# Control_Schem.net
KiCad netlist of a schematic drawn in Altium Designer
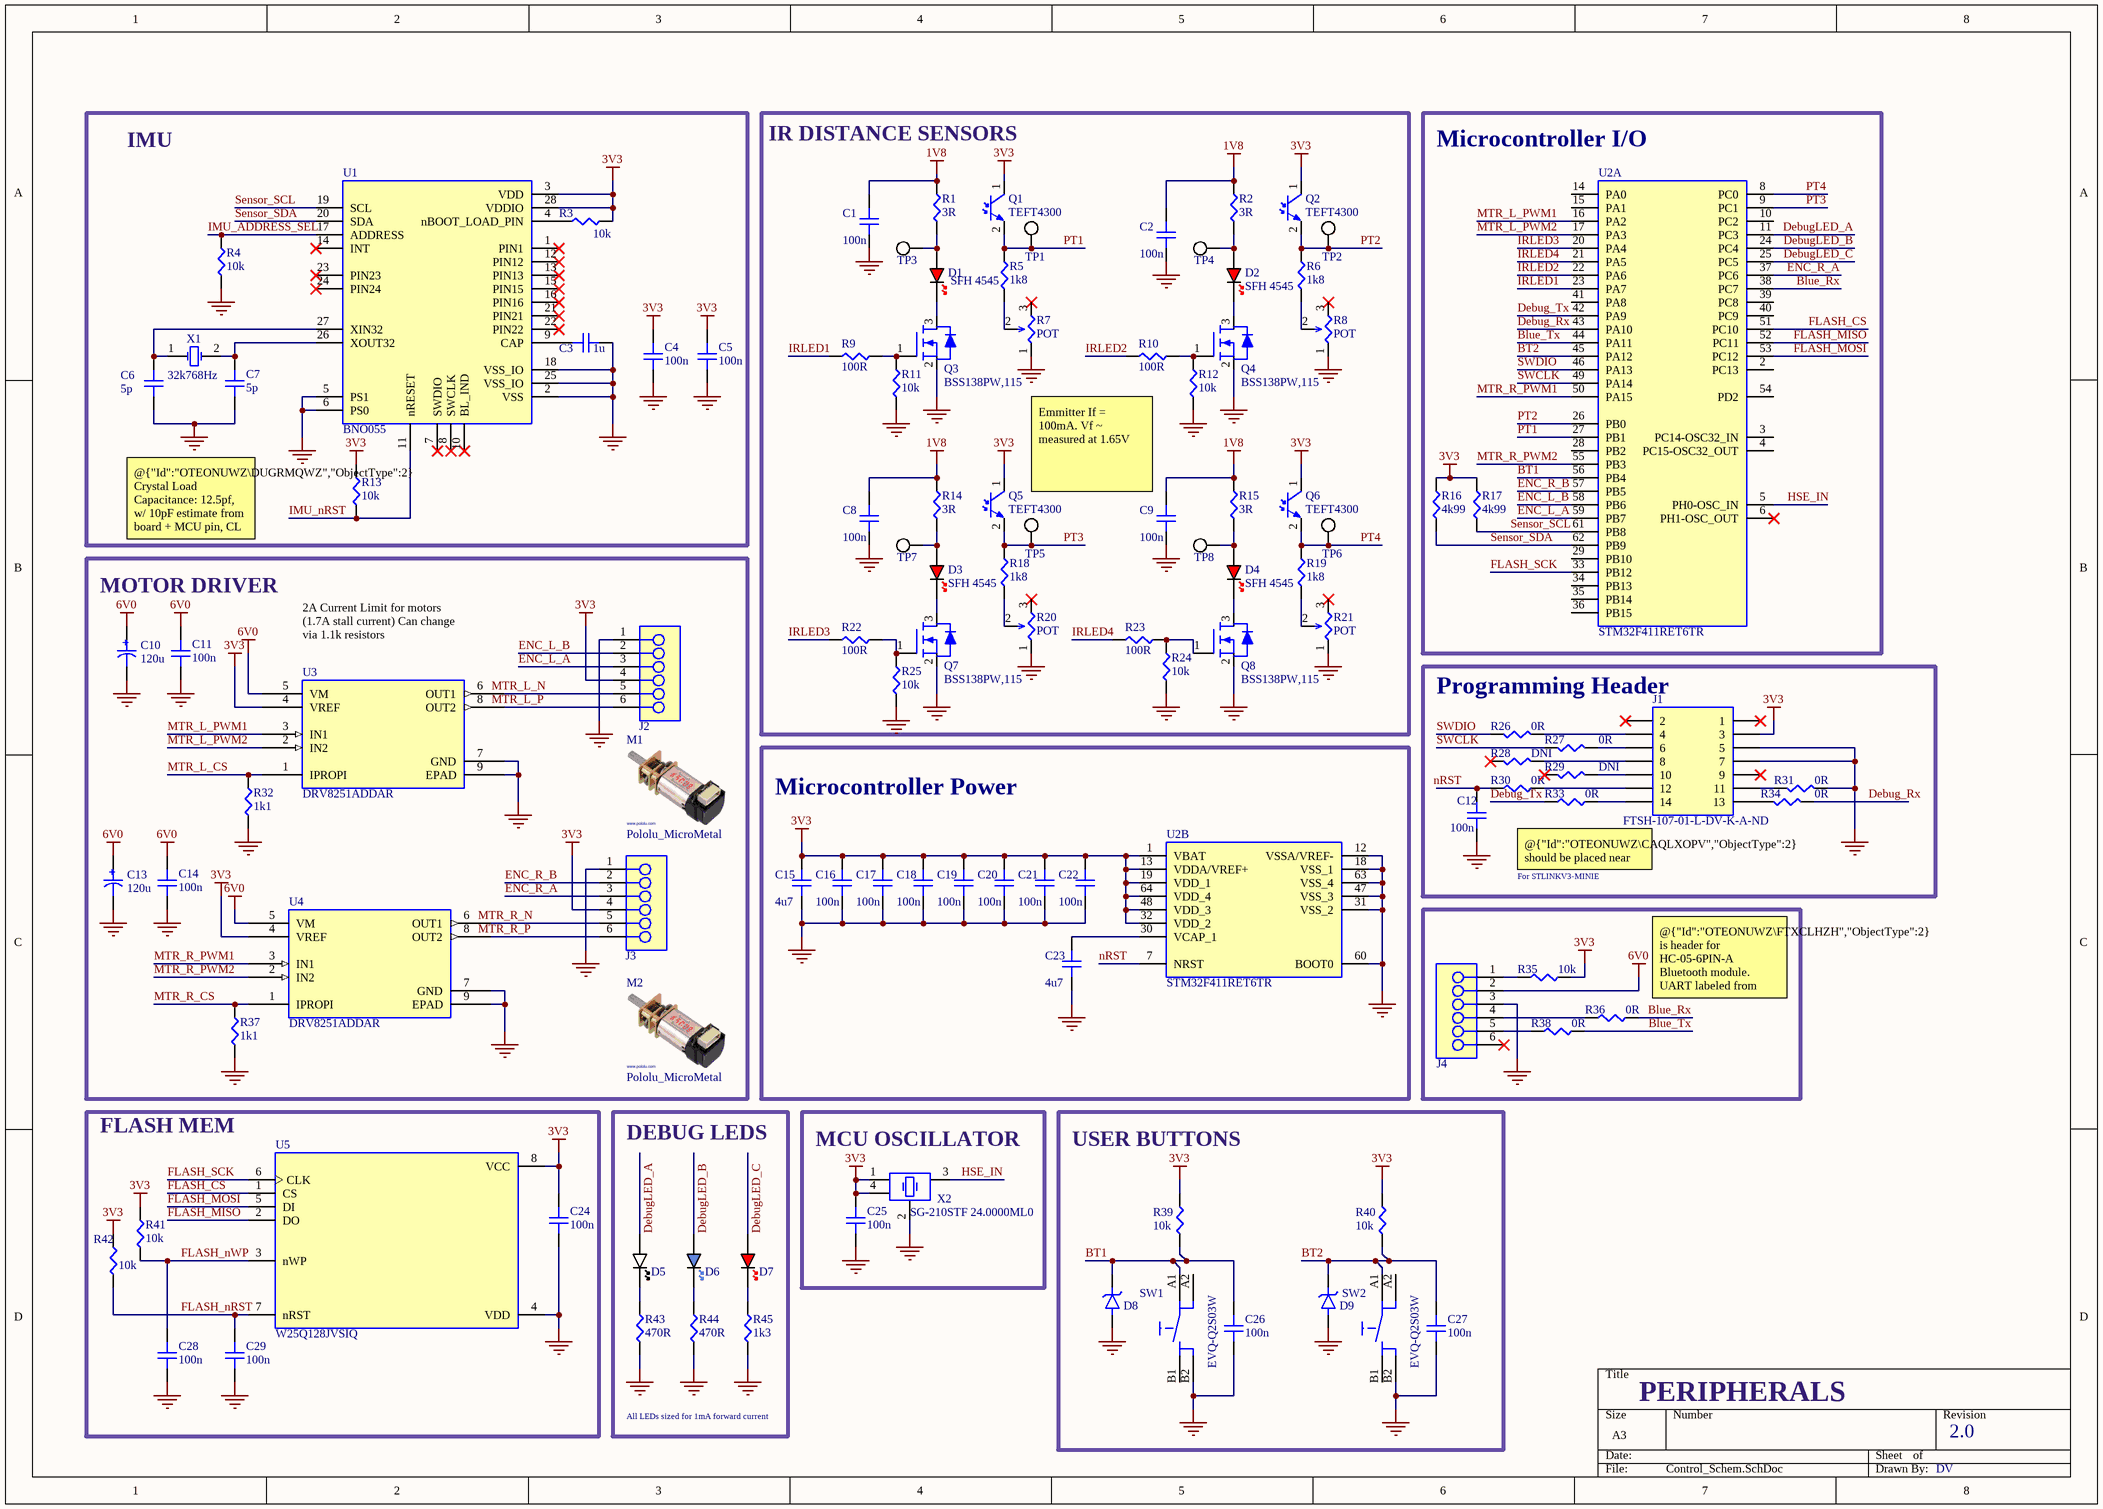
[diagram p0: Control_Schem.SchDoc]

(export (version "E")
  (design (tool "Eeschema 10.0.6"))
  (components
    (comp (ref "C1")
      (value "100n")
      (footprint "CAP_0603")
      (description "Multi Layer Ceramic Capacitor (MLCC) / Cap Ceramic 0.1uF 50V X7R 10% Pad SMD 0603 125°C T/R")
      (fields
        (field (name "MANUFACTURER") "Yageo Group")
        (field (name "MANUFACTURER PART NUMBER") "C0603C104K5RACTU")
      )
      (libsource (lib "Passives") (part "CAP"))
    )
    (comp (ref "C2")
      (value "100n")
      (footprint "CAP_0603")
      (description "Multi Layer Ceramic Capacitor (MLCC) / Cap Ceramic 0.1uF 50V X7R 10% Pad SMD 0603 125°C T/R")
      (fields
        (field (name "MANUFACTURER") "Yageo Group")
        (field (name "MANUFACTURER PART NUMBER") "C0603C104K5RACTU")
      )
      (libsource (lib "Passives") (part "CAP"))
    )
    (comp (ref "C3")
      (value "1u")
      (footprint "CAP_0603")
      (description "25V 1uF X7R 卤10% 0603 Multilayer Ceramic Capacitors MLCC - SMD/SMT ROHS")
      (fields
        (field (name "MANUFACTURER") "Samsung Electro-Mechanics")
        (field (name "MANUFACTURER PART NUMBER") "CL10B105KA8NNNC")
      )
      (libsource (lib "Standard") (part "CAP"))
    )
    (comp (ref "C4")
      (value "100n")
      (footprint "CAP_0603")
      (description "Multi Layer Ceramic Capacitor (MLCC) / Cap Ceramic 0.1uF 50V X7R 10% Pad SMD 0603 125°C T/R")
      (fields
        (field (name "MANUFACTURER") "Yageo Group")
        (field (name "MANUFACTURER PART NUMBER") "C0603C104K5RACTU")
      )
      (libsource (lib "Standard") (part "CAP"))
    )
    (comp (ref "C5")
      (value "100n")
      (footprint "CAP_0603")
      (description "Multi Layer Ceramic Capacitor (MLCC) / Cap Ceramic 0.1uF 50V X7R 10% Pad SMD 0603 125°C T/R")
      (fields
        (field (name "MANUFACTURER") "Yageo Group")
        (field (name "MANUFACTURER PART NUMBER") "C0603C104K5RACTU")
      )
      (libsource (lib "Standard") (part "CAP"))
    )
    (comp (ref "C6")
      (value "5p")
      (footprint "CAP_0603")
      (description "0603 5 pF 50 V ±0.25 pF Tolerance NP0 SMT Multilayer Ceramic Capacitor")
      (fields
        (field (name "MANUFACTURER") "Yageo Group")
        (field (name "MANUFACTURER PART NUMBER") "CC0402CRNPO9BN7R5")
      )
      (libsource (lib "Standard") (part "CAP"))
    )
    (comp (ref "C7")
      (value "5p")
      (footprint "CAP_0603")
      (description "0603 5 pF 50 V ±0.25 pF Tolerance NP0 SMT Multilayer Ceramic Capacitor")
      (fields
        (field (name "MANUFACTURER") "Yageo Group")
        (field (name "MANUFACTURER PART NUMBER") "CC0402CRNPO9BN7R5")
      )
      (libsource (lib "Standard") (part "CAP"))
    )
    (comp (ref "C8")
      (value "100n")
      (footprint "CAP_0603")
      (description "Multi Layer Ceramic Capacitor (MLCC) / Cap Ceramic 0.1uF 50V X7R 10% Pad SMD 0603 125°C T/R")
      (fields
        (field (name "MANUFACTURER") "Yageo Group")
        (field (name "MANUFACTURER PART NUMBER") "C0603C104K5RACTU")
      )
      (libsource (lib "Passives") (part "CAP"))
    )
    (comp (ref "C9")
      (value "100n")
      (footprint "CAP_0603")
      (description "Multi Layer Ceramic Capacitor (MLCC) / Cap Ceramic 0.1uF 50V X7R 10% Pad SMD 0603 125°C T/R")
      (fields
        (field (name "MANUFACTURER") "Yageo Group")
        (field (name "MANUFACTURER PART NUMBER") "C0603C104K5RACTU")
      )
      (libsource (lib "Passives") (part "CAP"))
    )
    (comp (ref "C10")
      (value "120u")
      (footprint "PCAP_SVP_C6_PAN-M")
      (description "Cap Aluminum Polymer 120uF 20VDC 20%( 6.3 X 5.9mm) SMD 0.025 Ohm 3.2A 5000h 105C T/R")
      (fields
        (field (name "MANUFACTURER") "Panasonic")
        (field (name "MANUFACTURER PART NUMBER") "20SVPF120M")
      )
      (libsource (lib "Standard") (part "CAP_ELECTROLYTIC"))
    )
    (comp (ref "C11")
      (value "100n")
      (footprint "CAP_0603")
      (description "Multi Layer Ceramic Capacitor (MLCC) / Cap Ceramic 0.1uF 50V X7R 10% Pad SMD 0603 125°C T/R")
      (fields
        (field (name "MANUFACTURER") "Yageo Group")
        (field (name "MANUFACTURER PART NUMBER") "C0603C104K5RACTU")
      )
      (libsource (lib "Standard") (part "CAP"))
    )
    (comp (ref "C12")
      (value "100n")
      (footprint "CAP_0603")
      (description "Multi Layer Ceramic Capacitor (MLCC) / Cap Ceramic 0.1uF 50V X7R 10% Pad SMD 0603 125°C T/R")
      (fields
        (field (name "MANUFACTURER") "Yageo Group")
        (field (name "MANUFACTURER PART NUMBER") "C0603C104K5RACTU")
      )
      (libsource (lib "Passives") (part "CAP"))
    )
    (comp (ref "C13")
      (value "120u")
      (footprint "PCAP_SVP_C6_PAN-M")
      (description "Cap Aluminum Polymer 120uF 20VDC 20%( 6.3 X 5.9mm) SMD 0.025 Ohm 3.2A 5000h 105C T/R")
      (fields
        (field (name "MANUFACTURER") "Panasonic")
        (field (name "MANUFACTURER PART NUMBER") "20SVPF120M")
      )
      (libsource (lib "Standard") (part "CAP_ELECTROLYTIC"))
    )
    (comp (ref "C14")
      (value "100n")
      (footprint "CAP_0603")
      (description "Multi Layer Ceramic Capacitor (MLCC) / Cap Ceramic 0.1uF 50V X7R 10% Pad SMD 0603 125°C T/R")
      (fields
        (field (name "MANUFACTURER") "Yageo Group")
        (field (name "MANUFACTURER PART NUMBER") "C0603C104K5RACTU")
      )
      (libsource (lib "Standard") (part "CAP"))
    )
    (comp (ref "C15")
      (value "4u7")
      (footprint "CAP_0603")
      (description "25V 4.7uF X6S ±10% 0603 Multilayer Ceramic Capacitors MLCC - SMD/SMT ROHS")
      (fields
        (field (name "MANUFACTURER") "Murata")
        (field (name "MANUFACTURER PART NUMBER") "GRT188C81E475KE13D")
      )
      (libsource (lib "Passives") (part "CAP"))
    )
    (comp (ref "C16")
      (value "100n")
      (footprint "CAP_0603")
      (description "Multi Layer Ceramic Capacitor (MLCC) / Cap Ceramic 0.1uF 50V X7R 10% Pad SMD 0603 125°C T/R")
      (fields
        (field (name "MANUFACTURER") "Yageo Group")
        (field (name "MANUFACTURER PART NUMBER") "C0603C104K5RACTU")
      )
      (libsource (lib "Passives") (part "CAP"))
    )
    (comp (ref "C17")
      (value "100n")
      (footprint "CAP_0603")
      (description "Multi Layer Ceramic Capacitor (MLCC) / Cap Ceramic 0.1uF 50V X7R 10% Pad SMD 0603 125°C T/R")
      (fields
        (field (name "MANUFACTURER") "Yageo Group")
        (field (name "MANUFACTURER PART NUMBER") "C0603C104K5RACTU")
      )
      (libsource (lib "Passives") (part "CAP"))
    )
    (comp (ref "C18")
      (value "100n")
      (footprint "CAP_0603")
      (description "Multi Layer Ceramic Capacitor (MLCC) / Cap Ceramic 0.1uF 50V X7R 10% Pad SMD 0603 125°C T/R")
      (fields
        (field (name "MANUFACTURER") "Yageo Group")
        (field (name "MANUFACTURER PART NUMBER") "C0603C104K5RACTU")
      )
      (libsource (lib "Passives") (part "CAP"))
    )
    (comp (ref "C19")
      (value "100n")
      (footprint "CAP_0603")
      (description "Multi Layer Ceramic Capacitor (MLCC) / Cap Ceramic 0.1uF 50V X7R 10% Pad SMD 0603 125°C T/R")
      (fields
        (field (name "MANUFACTURER") "Yageo Group")
        (field (name "MANUFACTURER PART NUMBER") "C0603C104K5RACTU")
      )
      (libsource (lib "Passives") (part "CAP"))
    )
    (comp (ref "C20")
      (value "100n")
      (footprint "CAP_0603")
      (description "Multi Layer Ceramic Capacitor (MLCC) / Cap Ceramic 0.1uF 50V X7R 10% Pad SMD 0603 125°C T/R")
      (fields
        (field (name "MANUFACTURER") "Yageo Group")
        (field (name "MANUFACTURER PART NUMBER") "C0603C104K5RACTU")
      )
      (libsource (lib "Passives") (part "CAP"))
    )
    (comp (ref "C21")
      (value "100n")
      (footprint "CAP_0603")
      (description "Multi Layer Ceramic Capacitor (MLCC) / Cap Ceramic 0.1uF 50V X7R 10% Pad SMD 0603 125°C T/R")
      (fields
        (field (name "MANUFACTURER") "Yageo Group")
        (field (name "MANUFACTURER PART NUMBER") "C0603C104K5RACTU")
      )
      (libsource (lib "Passives") (part "CAP"))
    )
    (comp (ref "C22")
      (value "100n")
      (footprint "CAP_0603")
      (description "Multi Layer Ceramic Capacitor (MLCC) / Cap Ceramic 0.1uF 50V X7R 10% Pad SMD 0603 125°C T/R")
      (fields
        (field (name "MANUFACTURER") "Yageo Group")
        (field (name "MANUFACTURER PART NUMBER") "C0603C104K5RACTU")
      )
      (libsource (lib "Passives") (part "CAP"))
    )
    (comp (ref "C23")
      (value "4u7")
      (footprint "CAP_0603")
      (description "25V 4.7uF X6S ±10% 0603 Multilayer Ceramic Capacitors MLCC - SMD/SMT ROHS")
      (fields
        (field (name "MANUFACTURER") "Murata")
        (field (name "MANUFACTURER PART NUMBER") "GRT188C81E475KE13D")
      )
      (libsource (lib "Passives") (part "CAP"))
    )
    (comp (ref "C24")
      (value "100n")
      (footprint "CAP_0603")
      (description "50V 100nF X7R ±10% 0603 Multilayer Ceramic Capacitors MLCC - SMD/SMT ROHS")
      (fields
        (field (name "MANUFACTURER") "Yageo Group")
        (field (name "MANUFACTURER PART NUMBER") "C0603C104K5RACTU")
      )
      (libsource (lib "Standard") (part "CAP"))
    )
    (comp (ref "C25")
      (value "100n")
      (footprint "CAP_0603")
      (description "Multi Layer Ceramic Capacitor (MLCC) / Cap Ceramic 0.1uF 50V X7R 10% Pad SMD 0603 125°C T/R")
      (fields
        (field (name "MANUFACTURER") "Yageo Group")
        (field (name "MANUFACTURER PART NUMBER") "C0603C104K5RACTU")
      )
      (libsource (lib "Standard") (part "CAP"))
    )
    (comp (ref "C26")
      (value "100n")
      (footprint "CAP_0603")
      (description "Multi Layer Ceramic Capacitor (MLCC) / Cap Ceramic 0.1uF 50V X7R 10% Pad SMD 0603 125°C T/R")
      (fields
        (field (name "MANUFACTURER") "Yageo Group")
        (field (name "MANUFACTURER PART NUMBER") "C0603C104K5RACTU")
      )
      (libsource (lib "Passives") (part "CAP"))
    )
    (comp (ref "C27")
      (value "100n")
      (footprint "CAP_0603")
      (description "Multi Layer Ceramic Capacitor (MLCC) / Cap Ceramic 0.1uF 50V X7R 10% Pad SMD 0603 125°C T/R")
      (fields
        (field (name "MANUFACTURER") "Yageo Group")
        (field (name "MANUFACTURER PART NUMBER") "C0603C104K5RACTU")
      )
      (libsource (lib "Passives") (part "CAP"))
    )
    (comp (ref "C28")
      (value "100n")
      (footprint "CAP_0603")
      (description "Multi Layer Ceramic Capacitor (MLCC) / Cap Ceramic 0.1uF 50V X7R 10% Pad SMD 0603 125°C T/R")
      (fields
        (field (name "MANUFACTURER") "Yageo Group")
        (field (name "MANUFACTURER PART NUMBER") "C0603C104K5RACTU")
      )
      (libsource (lib "Standard") (part "CAP"))
    )
    (comp (ref "C29")
      (value "100n")
      (footprint "CAP_0603")
      (description "Multi Layer Ceramic Capacitor (MLCC) / Cap Ceramic 0.1uF 50V X7R 10% Pad SMD 0603 125°C T/R")
      (fields
        (field (name "MANUFACTURER") "Yageo Group")
        (field (name "MANUFACTURER PART NUMBER") "C0603C104K5RACTU")
      )
      (libsource (lib "Standard") (part "CAP"))
    )
    (comp (ref "D1")
      (value "SFH 4545")
      (footprint "SFH4545")
      (description "Radial T1 3/4 Infrared LED Infrared LED, 5mm, 1-Element, 950nm")
      (fields (field (name "MANUFACTURER") "Osram"))
      (libsource (lib "Standard") (part "LED_Red"))
    )
    (comp (ref "D2")
      (value "SFH 4545")
      (footprint "SFH4545")
      (description "Radial T1 3/4 Infrared LED Infrared LED, 5mm, 1-Element, 950nm")
      (fields (field (name "MANUFACTURER") "Osram"))
      (libsource (lib "Standard") (part "LED_Red"))
    )
    (comp (ref "D3")
      (value "SFH 4545")
      (footprint "SFH4545")
      (description "Radial T1 3/4 Infrared LED Infrared LED, 5mm, 1-Element, 950nm")
      (fields (field (name "MANUFACTURER") "Osram"))
      (libsource (lib "Standard") (part "LED_Red"))
    )
    (comp (ref "D4")
      (value "SFH 4545")
      (footprint "SFH4545")
      (description "Radial T1 3/4 Infrared LED Infrared LED, 5mm, 1-Element, 950nm")
      (fields (field (name "MANUFACTURER") "Osram"))
      (libsource (lib "Standard") (part "LED_Red"))
    )
    (comp (ref "D5")
      (value "LED_White")
      (footprint "LED_0603")
      (description "White 1.6 x 0.8 x 0.55 mm 130° Tinted Yellow 180 mcd 3 V LED SMT")
      (fields
        (field (name "MANUFACTURER") "Diodes Inc.")
        (field (name "MANUFACTURER PART NUMBER") "LTW-C191DS5")
      )
      (libsource (lib "Standard") (part "LED_White"))
    )
    (comp (ref "D6")
      (value "LED_Blue")
      (footprint "LED_0603")
      (description "LED blue 0603 wavelength 465~475nm light intensity 15mcd Front Mounting")
      (fields
        (field (name "MANUFACTURER") "Diodes Inc.")
        (field (name "MANUFACTURER PART NUMBER") "LTST-C193TBKT-5A")
      )
      (libsource (lib "Standard") (part "LED_Blue"))
    )
    (comp (ref "D7")
      (value "LED_Red")
      (footprint "LED_0603")
      (description "Single-color LEDs; LITEON; LTST-C193KRKT-5A; Red; 130 °; 2.3 V; 0603")
      (fields
        (field (name "MANUFACTURER") "Diodes Inc.")
        (field (name "MANUFACTURER PART NUMBER") "LTST-C193KRKT-5A")
      )
      (libsource (lib "Standard") (part "LED_Red"))
    )
    (comp (ref "D8")
      (value "65pF")
      (footprint "SOD-923")
      (description "ESD9X5.0ST5G Series 6.2 V 65 pF TVS Diode for ESD Protection - SOD-923")
      (fields (field (name "MANUFACTURER") "onsemi") (field (name "MANUFACTURER PART NUMBER") "ESD9X5.0ST5G"))
      (libsource (lib "Standard") (part "Zenner"))
    )
    (comp (ref "D9")
      (value "65pF")
      (footprint "SOD-923")
      (description "ESD9X5.0ST5G Series 6.2 V 65 pF TVS Diode for ESD Protection - SOD-923")
      (fields (field (name "MANUFACTURER") "onsemi") (field (name "MANUFACTURER PART NUMBER") "ESD9X5.0ST5G"))
      (libsource (lib "Standard") (part "Zenner"))
    )
    (comp (ref "J1")
      (value "STDC14_DebugConnector")
      (footprint "STM32_ProgrammingHeader")
      (fields (field (name "SUPPLIER PART NUMBER 1") "FTSH-107-01-L-DV-K-A-ND"))
      (libsource (lib "ST_Microcontroller") (part "STDC14_DebugConnector"))
    )
    (comp (ref "J2")
      (value "6POS")
      (footprint "JST_BM06B-SRSS-TB")
      (description "Connector Header, SR Series, 6 Position, 1.00mm, 50V, Surface Mount, Tin, Natural")
      (fields
        (field (name "MANUFACTURER") "JST")
        (field (name "MANUFACTURER PART NUMBER") "BM06B-SRSS-TB(LF)(SN)")
      )
      (libsource (lib "Connectors") (part "6POS"))
    )
    (comp (ref "J3")
      (value "6POS")
      (footprint "JST_BM06B-SRSS-TB")
      (description "Connector Header, SR Series, 6 Position, 1.00mm, 50V, Surface Mount, Tin, Natural")
      (fields
        (field (name "MANUFACTURER") "JST")
        (field (name "MANUFACTURER PART NUMBER") "BM06B-SRSS-TB(LF)(SN)")
      )
      (libsource (lib "Connectors") (part "6POS"))
    )
    (comp (ref "J4")
      (value "6POS")
      (footprint "P2.54_6POS")
      (description "Connector Header, SR Series, 6 Position, 1.00mm, 50V, Surface Mount, Tin, Natural")
      (libsource (lib "") (part "6POS_1"))
    )
    (comp (ref "M1")
      (value "Pololu_MicroMetal")
      (footprint "PololuMicroMetal")
      (libsource (lib "Motion") (part "Pololu_MicroMetal"))
    )
    (comp (ref "M2")
      (value "Pololu_MicroMetal")
      (footprint "PololuMicroMetal")
      (libsource (lib "Motion") (part "Pololu_MicroMetal"))
    )
    (comp (ref "Q1")
      (value "TEFT4300")
      (footprint "TEFT4300")
      (description "TEFT4300 Series 925 nm ±60° 70 V 50 mA Silicon NPN Phototransistor - T-5")
      (fields (field (name "MANUFACTURER") "Vishay"))
      (libsource (lib "Standard") (part "NPN_PHOTOTRANSISTOR"))
    )
    (comp (ref "Q2")
      (value "TEFT4300")
      (footprint "TEFT4300")
      (description "TEFT4300 Series 925 nm ±60° 70 V 50 mA Silicon NPN Phototransistor - T-5")
      (fields (field (name "MANUFACTURER") "Vishay"))
      (libsource (lib "Standard") (part "NPN_PHOTOTRANSISTOR"))
    )
    (comp (ref "Q3")
      (value "BSS138PW,115")
      (footprint "SOT23-3")
      (description "Transistor MOSFET N-CH 60V 0.32A Automotive 3-Pin SC-70 T/R")
      (fields (field (name "MANUFACTURER") "Nexperia"))
      (libsource (lib "Standard") (part "NMOS"))
    )
    (comp (ref "Q4")
      (value "BSS138PW,115")
      (footprint "SOT23-3")
      (description "Transistor MOSFET N-CH 60V 0.32A Automotive 3-Pin SC-70 T/R")
      (fields (field (name "MANUFACTURER") "Nexperia"))
      (libsource (lib "Standard") (part "NMOS"))
    )
    (comp (ref "Q5")
      (value "TEFT4300")
      (footprint "TEFT4300")
      (description "TEFT4300 Series 925 nm ±60° 70 V 50 mA Silicon NPN Phototransistor - T-5")
      (fields (field (name "MANUFACTURER") "Vishay"))
      (libsource (lib "Standard") (part "NPN_PHOTOTRANSISTOR"))
    )
    (comp (ref "Q6")
      (value "TEFT4300")
      (footprint "TEFT4300")
      (description "TEFT4300 Series 925 nm ±60° 70 V 50 mA Silicon NPN Phototransistor - T-5")
      (fields (field (name "MANUFACTURER") "Vishay"))
      (libsource (lib "Standard") (part "NPN_PHOTOTRANSISTOR"))
    )
    (comp (ref "Q7")
      (value "BSS138PW,115")
      (footprint "SOT23-3")
      (description "Transistor MOSFET N-CH 60V 0.32A Automotive 3-Pin SC-70 T/R")
      (fields (field (name "MANUFACTURER") "Nexperia"))
      (libsource (lib "Standard") (part "NMOS"))
    )
    (comp (ref "Q8")
      (value "BSS138PW,115")
      (footprint "SOT23-3")
      (description "Transistor MOSFET N-CH 60V 0.32A Automotive 3-Pin SC-70 T/R")
      (fields (field (name "MANUFACTURER") "Nexperia"))
      (libsource (lib "Standard") (part "NMOS"))
    )
    (comp (ref "R1")
      (value "3R")
      (footprint "RES_0603")
      (description "100mW Thick Film Resistors 75V ±5% ±200ppm/℃ 3Ω 0603 Chip Resistor - Surface Mount ROHS")
      (fields
        (field (name "MANUFACTURER") "Yageo Group")
        (field (name "MANUFACTURER PART NUMBER") "RC0603JR-073RL")
      )
      (libsource (lib "Standard") (part "RES"))
    )
    (comp (ref "R2")
      (value "3R")
      (footprint "RES_0603")
      (description "100mW Thick Film Resistors 75V ±5% ±200ppm/℃ 3Ω 0603 Chip Resistor - Surface Mount ROHS")
      (fields
        (field (name "MANUFACTURER") "Yageo Group")
        (field (name "MANUFACTURER PART NUMBER") "RC0603JR-073RL")
      )
      (libsource (lib "Standard") (part "RES"))
    )
    (comp (ref "R3")
      (value "10k")
      (footprint "RES_0603")
      (description "100mW Thick Film Resistors ±100ppm/℃ ±1% 10kΩ 0603 Chip Resistor - Surface Mount ROHS")
      (fields
        (field (name "MANUFACTURER") "Yageo Group")
        (field (name "MANUFACTURER PART NUMBER") "RC0603FR-0710KL")
      )
      (libsource (lib "Standard") (part "RES"))
    )
    (comp (ref "R4")
      (value "10k")
      (footprint "RES_0603")
      (description "100mW Thick Film Resistors ±100ppm/℃ ±1% 10kΩ 0603 Chip Resistor - Surface Mount ROHS")
      (fields
        (field (name "MANUFACTURER") "Yageo Group")
        (field (name "MANUFACTURER PART NUMBER") "RC0603FR-0710KL")
      )
      (libsource (lib "Standard") (part "RES"))
    )
    (comp (ref "R5")
      (value "1k8")
      (footprint "RES_0603")
      (description "General Purpose Chip Resistors RC0603 Rohs Compliant ¦ Res SMD 1.8K Ohm 1% 1/10W 0603")
      (fields
        (field (name "MANUFACTURER") "Yageo Group")
        (field (name "MANUFACTURER PART NUMBER") "RC0603FR-071K8L")
      )
      (libsource (lib "Standard") (part "RES"))
    )
    (comp (ref "R6")
      (value "1k8")
      (footprint "RES_0603")
      (description "General Purpose Chip Resistors RC0603 Rohs Compliant ¦ Res SMD 1.8K Ohm 1% 1/10W 0603")
      (fields
        (field (name "MANUFACTURER") "Yageo Group")
        (field (name "MANUFACTURER PART NUMBER") "RC0603FR-071K8L")
      )
      (libsource (lib "Standard") (part "RES"))
    )
    (comp (ref "R7")
      (value "POT")
      (footprint "TRIM_3296Y-1-203LF")
      (description "Cermet Not Linear TRIMMER Trimmer Potentiometer ±10% 500mW 70C 300V")
      (fields
        (field (name "MANUFACTURER") "Bourns")
        (field (name "MANUFACTURER PART NUMBER") "3296W-1-203LF")
      )
      (libsource (lib "Standard") (part "POT"))
    )
    (comp (ref "R8")
      (value "POT")
      (footprint "TRIM_3296Y-1-203LF")
      (description "Cermet Not Linear TRIMMER Trimmer Potentiometer ±10% 500mW 70C 300V")
      (fields
        (field (name "MANUFACTURER") "Bourns")
        (field (name "MANUFACTURER PART NUMBER") "3296W-1-203LF")
      )
      (libsource (lib "Standard") (part "POT"))
    )
    (comp (ref "R9")
      (value "100R")
      (footprint "RES_0603")
      (description "Yageo RC0603FR-07100RL 0603 SMD Resistor 100 Ohm thin film chip resistor")
      (fields
        (field (name "MANUFACTURER") "Yageo Group")
        (field (name "MANUFACTURER PART NUMBER") "RC0603FR-07100RL")
      )
      (libsource (lib "Standard") (part "RES"))
    )
    (comp (ref "R10")
      (value "100R")
      (footprint "RES_0603")
      (description "Yageo RC0603FR-07100RL 0603 SMD Resistor 100 Ohm thin film chip resistor")
      (fields
        (field (name "MANUFACTURER") "Yageo Group")
        (field (name "MANUFACTURER PART NUMBER") "RC0603FR-07100RL")
      )
      (libsource (lib "Standard") (part "RES"))
    )
    (comp (ref "R11")
      (value "10k")
      (footprint "RES_0603")
      (description "Fixed Resistor, Thin Film, 0.125W, 49.9ohm, 150V, 1% +/-Tol, 100ppm/Cel, Surface Mount, 0603")
      (fields
        (field (name "MANUFACTURER") "Stackpole Electronics")
        (field (name "MANUFACTURER PART NUMBER") "RNCP0603FTD49R9")
      )
      (libsource (lib "Standard") (part "RES"))
    )
    (comp (ref "R12")
      (value "10k")
      (footprint "RES_0603")
      (description "Fixed Resistor, Thin Film, 0.125W, 49.9ohm, 150V, 1% +/-Tol, 100ppm/Cel, Surface Mount, 0603")
      (fields
        (field (name "MANUFACTURER") "Stackpole Electronics")
        (field (name "MANUFACTURER PART NUMBER") "RNCP0603FTD49R9")
      )
      (libsource (lib "Standard") (part "RES"))
    )
    (comp (ref "R13")
      (value "10k")
      (footprint "RES_0603")
      (description "100mW Thick Film Resistors ±100ppm/℃ ±1% 10kΩ 0603 Chip Resistor - Surface Mount ROHS")
      (fields
        (field (name "MANUFACTURER") "Yageo Group")
        (field (name "MANUFACTURER PART NUMBER") "RC0603FR-0710KL")
      )
      (libsource (lib "Standard") (part "RES"))
    )
    (comp (ref "R14")
      (value "3R")
      (footprint "RES_0603")
      (description "100mW Thick Film Resistors 75V ±5% ±200ppm/℃ 3Ω 0603 Chip Resistor - Surface Mount ROHS")
      (fields
        (field (name "MANUFACTURER") "Yageo Group")
        (field (name "MANUFACTURER PART NUMBER") "RC0603JR-073RL")
      )
      (libsource (lib "Standard") (part "RES"))
    )
    (comp (ref "R15")
      (value "3R")
      (footprint "RES_0603")
      (description "100mW Thick Film Resistors 75V ±5% ±200ppm/℃ 3Ω 0603 Chip Resistor - Surface Mount ROHS")
      (fields
        (field (name "MANUFACTURER") "Yageo Group")
        (field (name "MANUFACTURER PART NUMBER") "RC0603JR-073RL")
      )
      (libsource (lib "Standard") (part "RES"))
    )
    (comp (ref "R16")
      (value "4k99")
      (footprint "RES_0603")
      (description "100mW Thick Film Resistors 75V ±100ppm/℃ ±1% 4.99kΩ 0603 Chip Resistor - Surface Mount ROHS")
      (fields
        (field (name "MANUFACTURER") "Yageo Group")
        (field (name "MANUFACTURER PART NUMBER") "RC0603FR-074K99L")
      )
      (libsource (lib "Standard") (part "RES"))
    )
    (comp (ref "R17")
      (value "4k99")
      (footprint "RES_0603")
      (description "100mW Thick Film Resistors 75V ±100ppm/℃ ±1% 4.99kΩ 0603 Chip Resistor - Surface Mount ROHS")
      (fields
        (field (name "MANUFACTURER") "Yageo Group")
        (field (name "MANUFACTURER PART NUMBER") "RC0603FR-074K99L")
      )
      (libsource (lib "Standard") (part "RES"))
    )
    (comp (ref "R18")
      (value "1k8")
      (footprint "RES_0603")
      (description "General Purpose Chip Resistors RC0603 Rohs Compliant ¦ Res SMD 1.8K Ohm 1% 1/10W 0603")
      (fields
        (field (name "MANUFACTURER") "Yageo Group")
        (field (name "MANUFACTURER PART NUMBER") "RC0603FR-071K8L")
      )
      (libsource (lib "Standard") (part "RES"))
    )
    (comp (ref "R19")
      (value "1k8")
      (footprint "RES_0603")
      (description "General Purpose Chip Resistors RC0603 Rohs Compliant ¦ Res SMD 1.8K Ohm 1% 1/10W 0603")
      (fields
        (field (name "MANUFACTURER") "Yageo Group")
        (field (name "MANUFACTURER PART NUMBER") "RC0603FR-071K8L")
      )
      (libsource (lib "Standard") (part "RES"))
    )
    (comp (ref "R20")
      (value "POT")
      (footprint "TRIM_3296Y-1-203LF")
      (description "Cermet Not Linear TRIMMER Trimmer Potentiometer ±10% 500mW 70C 300V")
      (fields
        (field (name "MANUFACTURER") "Bourns")
        (field (name "MANUFACTURER PART NUMBER") "3296W-1-203LF")
      )
      (libsource (lib "Standard") (part "POT"))
    )
    (comp (ref "R21")
      (value "POT")
      (footprint "TRIM_3296Y-1-203LF")
      (description "Cermet Not Linear TRIMMER Trimmer Potentiometer ±10% 500mW 70C 300V")
      (fields
        (field (name "MANUFACTURER") "Bourns")
        (field (name "MANUFACTURER PART NUMBER") "3296W-1-203LF")
      )
      (libsource (lib "Standard") (part "POT"))
    )
    (comp (ref "R22")
      (value "100R")
      (footprint "RES_0603")
      (description "Yageo RC0603FR-07100RL 0603 SMD Resistor 100 Ohm thin film chip resistor")
      (fields
        (field (name "MANUFACTURER") "Yageo Group")
        (field (name "MANUFACTURER PART NUMBER") "RC0603FR-07100RL")
      )
      (libsource (lib "Standard") (part "RES"))
    )
    (comp (ref "R23")
      (value "100R")
      (footprint "RES_0603")
      (description "Yageo RC0603FR-07100RL 0603 SMD Resistor 100 Ohm thin film chip resistor")
      (fields
        (field (name "MANUFACTURER") "Yageo Group")
        (field (name "MANUFACTURER PART NUMBER") "RC0603FR-07100RL")
      )
      (libsource (lib "Standard") (part "RES"))
    )
    (comp (ref "R24")
      (value "10k")
      (footprint "RES_0603")
      (description "Fixed Resistor, Thin Film, 0.125W, 49.9ohm, 150V, 1% +/-Tol, 100ppm/Cel, Surface Mount, 0603")
      (fields
        (field (name "MANUFACTURER") "Stackpole Electronics")
        (field (name "MANUFACTURER PART NUMBER") "RNCP0603FTD49R9")
      )
      (libsource (lib "Standard") (part "RES"))
    )
    (comp (ref "R25")
      (value "10k")
      (footprint "RES_0603")
      (description "Fixed Resistor, Thin Film, 0.125W, 49.9ohm, 150V, 1% +/-Tol, 100ppm/Cel, Surface Mount, 0603")
      (fields
        (field (name "MANUFACTURER") "Stackpole Electronics")
        (field (name "MANUFACTURER PART NUMBER") "RNCP0603FTD49R9")
      )
      (libsource (lib "Standard") (part "RES"))
    )
    (comp (ref "R26")
      (value "0R")
      (footprint "RES_0603")
      (description "Fixed Resistor, Thin Film, 0.125W, 49.9ohm, 150V, 1% +/-Tol, 100ppm/Cel, Surface Mount, 0603")
      (fields
        (field (name "MANUFACTURER") "Stackpole Electronics")
        (field (name "MANUFACTURER PART NUMBER") "RNCP0603FTD49R9")
      )
      (libsource (lib "Passives") (part "RES"))
    )
    (comp (ref "R27")
      (value "0R")
      (footprint "RES_0603")
      (description "Fixed Resistor, Thin Film, 0.125W, 49.9ohm, 150V, 1% +/-Tol, 100ppm/Cel, Surface Mount, 0603")
      (fields
        (field (name "MANUFACTURER") "Stackpole Electronics")
        (field (name "MANUFACTURER PART NUMBER") "RNCP0603FTD49R9")
      )
      (libsource (lib "Passives") (part "RES"))
    )
    (comp (ref "R28")
      (value "DNI")
      (footprint "RES_0603")
      (description "Fixed Resistor, Thin Film, 0.125W, 49.9ohm, 150V, 1% +/-Tol, 100ppm/Cel, Surface Mount, 0603")
      (fields
        (field (name "MANUFACTURER") "Stackpole Electronics")
        (field (name "MANUFACTURER PART NUMBER") "RNCP0603FTD49R9")
      )
      (libsource (lib "Passives") (part "RES"))
    )
    (comp (ref "R29")
      (value "DNI")
      (footprint "RES_0603")
      (description "Fixed Resistor, Thin Film, 0.125W, 49.9ohm, 150V, 1% +/-Tol, 100ppm/Cel, Surface Mount, 0603")
      (fields
        (field (name "MANUFACTURER") "Stackpole Electronics")
        (field (name "MANUFACTURER PART NUMBER") "RNCP0603FTD49R9")
      )
      (libsource (lib "Passives") (part "RES"))
    )
    (comp (ref "R30")
      (value "0R")
      (footprint "RES_0603")
      (description "Fixed Resistor, Thin Film, 0.125W, 49.9ohm, 150V, 1% +/-Tol, 100ppm/Cel, Surface Mount, 0603")
      (fields
        (field (name "MANUFACTURER") "Stackpole Electronics")
        (field (name "MANUFACTURER PART NUMBER") "RNCP0603FTD49R9")
      )
      (libsource (lib "Passives") (part "RES"))
    )
    (comp (ref "R31")
      (value "0R")
      (footprint "RES_0603")
      (description "Fixed Resistor, Thin Film, 0.125W, 49.9ohm, 150V, 1% +/-Tol, 100ppm/Cel, Surface Mount, 0603")
      (fields
        (field (name "MANUFACTURER") "Stackpole Electronics")
        (field (name "MANUFACTURER PART NUMBER") "RNCP0603FTD49R9")
      )
      (libsource (lib "Passives") (part "RES"))
    )
    (comp (ref "R32")
      (value "1k1")
      (footprint "RES_0603")
      (description "Res General Purpose Thick Film 0603 1.1k Ohm 1% 1/10W ±100ppm/°C Molded Paper T/R")
      (fields
        (field (name "MANUFACTURER") "Yageo Group")
        (field (name "MANUFACTURER PART NUMBER") "RC0603FR-071K1L")
      )
      (libsource (lib "Standard") (part "RES"))
    )
    (comp (ref "R33")
      (value "0R")
      (footprint "RES_0603")
      (description "Fixed Resistor, Thin Film, 0.125W, 49.9ohm, 150V, 1% +/-Tol, 100ppm/Cel, Surface Mount, 0603")
      (fields
        (field (name "MANUFACTURER") "Stackpole Electronics")
        (field (name "MANUFACTURER PART NUMBER") "RNCP0603FTD49R9")
      )
      (libsource (lib "Passives") (part "RES"))
    )
    (comp (ref "R34")
      (value "0R")
      (footprint "RES_0603")
      (description "Fixed Resistor, Thin Film, 0.125W, 49.9ohm, 150V, 1% +/-Tol, 100ppm/Cel, Surface Mount, 0603")
      (fields
        (field (name "MANUFACTURER") "Stackpole Electronics")
        (field (name "MANUFACTURER PART NUMBER") "RNCP0603FTD49R9")
      )
      (libsource (lib "Passives") (part "RES"))
    )
    (comp (ref "R35")
      (value "10k")
      (footprint "RES_0603")
      (description "100mW Thick Film Resistors ±100ppm/℃ ±1% 10kΩ 0603 Chip Resistor - Surface Mount ROHS")
      (fields
        (field (name "MANUFACTURER") "Stackpole Electronics")
        (field (name "MANUFACTURER PART NUMBER") "RNCP0603FTD49R9")
      )
      (libsource (lib "Passives") (part "RES"))
    )
    (comp (ref "R36")
      (value "0R")
      (footprint "RES_0603")
      (description "GENERAL PURPOSE CHIP RESISTOR Metal Glaze/thick Film, 0.1W, 0ohm, Surface Mount, 0603")
      (fields
        (field (name "MANUFACTURER") "Stackpole Electronics")
        (field (name "MANUFACTURER PART NUMBER") "RNCP0603FTD49R9")
      )
      (libsource (lib "Passives") (part "RES"))
    )
    (comp (ref "R37")
      (value "1k1")
      (footprint "RES_0603")
      (description "Res General Purpose Thick Film 0603 1.1k Ohm 1% 1/10W ±100ppm/°C Molded Paper T/R")
      (fields
        (field (name "MANUFACTURER") "Yageo Group")
        (field (name "MANUFACTURER PART NUMBER") "RC0603FR-071K1L")
      )
      (libsource (lib "Standard") (part "RES"))
    )
    (comp (ref "R38")
      (value "0R")
      (footprint "RES_0603")
      (description "GENERAL PURPOSE CHIP RESISTOR Metal Glaze/thick Film, 0.1W, 0ohm, Surface Mount, 0603")
      (fields
        (field (name "MANUFACTURER") "Stackpole Electronics")
        (field (name "MANUFACTURER PART NUMBER") "RNCP0603FTD49R9")
      )
      (libsource (lib "Passives") (part "RES"))
    )
    (comp (ref "R39")
      (value "10k")
      (footprint "RES_0603")
      (description "100mW Thick Film Resistors ±100ppm/℃ ±1% 10kΩ 0603 Chip Resistor - Surface Mount ROHS")
      (fields
        (field (name "MANUFACTURER") "Yageo Group")
        (field (name "MANUFACTURER PART NUMBER") "RC0603FR-0710KL")
      )
      (libsource (lib "Standard") (part "RES"))
    )
    (comp (ref "R40")
      (value "10k")
      (footprint "RES_0603")
      (description "100mW Thick Film Resistors ±100ppm/℃ ±1% 10kΩ 0603 Chip Resistor - Surface Mount ROHS")
      (fields
        (field (name "MANUFACTURER") "Yageo Group")
        (field (name "MANUFACTURER PART NUMBER") "RC0603FR-0710KL")
      )
      (libsource (lib "Standard") (part "RES"))
    )
    (comp (ref "R41")
      (value "10k")
      (footprint "RES_0603")
      (description "100mW Thick Film Resistors ±100ppm/℃ ±1% 10kΩ 0603 Chip Resistor - Surface Mount ROHS")
      (fields
        (field (name "MANUFACTURER") "Yageo Group")
        (field (name "MANUFACTURER PART NUMBER") "RC0603FR-0710KL")
      )
      (libsource (lib "Standard") (part "RES"))
    )
    (comp (ref "R42")
      (value "10k")
      (footprint "RES_0603")
      (description "100mW Thick Film Resistors ±100ppm/℃ ±1% 10kΩ 0603 Chip Resistor - Surface Mount ROHS")
      (fields
        (field (name "MANUFACTURER") "Yageo Group")
        (field (name "MANUFACTURER PART NUMBER") "RC0603FR-0710KL")
      )
      (libsource (lib "Standard") (part "RES"))
    )
    (comp (ref "R43")
      (value "470R")
      (footprint "RES_0603")
      (description "Res Thick Film 0603 470 Ohm 1% 0.1W(1/10W) ±100ppm/C Pad SMD T/R")
      (fields
        (field (name "MANUFACTURER") "Yageo Group")
        (field (name "MANUFACTURER PART NUMBER") "RC0603FR-07470RL")
      )
      (libsource (lib "Standard") (part "RES"))
    )
    (comp (ref "R44")
      (value "470R")
      (footprint "RES_0603")
      (description "Res Thick Film 0603 470 Ohm 1% 0.1W(1/10W) ±100ppm/C Pad SMD T/R")
      (fields
        (field (name "MANUFACTURER") "Yageo Group")
        (field (name "MANUFACTURER PART NUMBER") "RC0603FR-07470RL")
      )
      (libsource (lib "Standard") (part "RES"))
    )
    (comp (ref "R45")
      (value "1k3")
      (footprint "RES_0603")
      (description "100mW Thick Film Resistors 75V ±100ppm/℃ ±5% 1.3kΩ 0603 Chip Resistor - Surface Mount ROHS")
      (fields
        (field (name "MANUFACTURER") "Yageo Group")
        (field (name "MANUFACTURER PART NUMBER") "RC0603JR-071K3L")
      )
      (libsource (lib "Standard") (part "RES"))
    )
    (comp (ref "SW1")
      (value "EVQ-Q2S03W")
      (footprint "EVQQ2S03W")
      (description "Switch Tactile ON OFF SPST Round Button J-Bend 0.02A 15VDC 1.6N SMD Embossed T/R")
      (fields (field (name "MOUSER PART NUMBER") "667-EVQ-Q2S03W") (field (name "MANUFACTURER") "Panasonic"))
      (libsource (lib "Standard") (part "SW"))
    )
    (comp (ref "SW2")
      (value "EVQ-Q2S03W")
      (footprint "EVQQ2S03W")
      (description "Switch Tactile ON OFF SPST Round Button J-Bend 0.02A 15VDC 1.6N SMD Embossed T/R")
      (fields (field (name "MOUSER PART NUMBER") "667-EVQ-Q2S03W") (field (name "MANUFACTURER") "Panasonic"))
      (libsource (lib "Standard") (part "SW"))
    )
    (comp (ref "TP1") (value "TP") (footprint "TP-TH") (libsource (lib "Standard") (part "TP")))
    (comp (ref "TP2") (value "TP") (footprint "TP-TH") (libsource (lib "Standard") (part "TP")))
    (comp (ref "TP3") (value "TP") (footprint "TP-TH") (libsource (lib "Standard") (part "TP")))
    (comp (ref "TP4") (value "TP") (footprint "TP-TH") (libsource (lib "Standard") (part "TP")))
    (comp (ref "TP5") (value "TP") (footprint "TP-TH") (libsource (lib "Standard") (part "TP")))
    (comp (ref "TP6") (value "TP") (footprint "TP-TH") (libsource (lib "Standard") (part "TP")))
    (comp (ref "TP7") (value "TP") (footprint "TP-TH") (libsource (lib "Standard") (part "TP")))
    (comp (ref "TP8") (value "TP") (footprint "TP-TH") (libsource (lib "Standard") (part "TP")))
    (comp (ref "U1")
      (value "BNO055")
      (footprint "LGA28_5.2X3.8")
      (description "IMU ACCEL/GYRO/MAG I2C 28LGA / Intelligent 9-axis absolute orientation sensor")
      (fields (field (name "MANUFACTURER") "Bosch Sensortec"))
      (libsource (lib "Bosch_Sensor") (part "BNO055"))
    )
    (comp (ref "U2")
      (value "STM32F411RET6TR")
      (footprint "LQFP-64_10X10")
      (description "RISC Microcontroller, 32-Bit, FLASH, CORTEX-M4 CPU, 100MHz, CMOS, PQFP64")
      (fields
        (field (name "MOUSER PART NUMBER") "511-STM32F411RET6TR")
        (field (name "MANUFACTURER") "STMicroelectronics")
      )
      (libsource (lib "ST_Microcontroller") (part "STM32F411RET6TR"))
    )
    (comp (ref "U3")
      (value "DRV8251ADDAR")
      (footprint "SOIC-8_EPAD")
      (fields (field (name "MANUFACTURER") "Texas Instruments"))
      (libsource (lib "Motion") (part "DRV8231ADSGR"))
    )
    (comp (ref "U4")
      (value "DRV8251ADDAR")
      (footprint "SOIC-8_EPAD")
      (fields (field (name "MANUFACTURER") "Texas Instruments"))
      (libsource (lib "Motion") (part "DRV8231ADSGR"))
    )
    (comp (ref "U5")
      (value "W25Q128JVSIQ")
      (footprint "SOIC-8")
      (description "NOR Flash Serial (SPI, Dual SPI, Quad SPI) 3.3V 128M-bit 16M x 8 6ns 8-Pin SOIC Tube")
      (fields (field (name "MANUFACTURER") "Winbond"))
      (libsource (lib "Memory") (part "W25Q128JVSIQ"))
    )
    (comp (ref "X1")
      (value "32k768Hz")
      (footprint "FP-ABS07-MFG")
      (description "Crystal 0.032768MHz ±20ppm (Tol) 12.5pF Flexural 70000Ohm 2-Pin CSMD T/R")
      (fields
        (field (name "MANUFACTURER") "Abracon")
        (field (name "MANUFACTURER PART NUMBER") "ABS07-32.768KHZ-T")
      )
      (libsource (lib "Standard") (part "XTAL-2P"))
    )
    (comp (ref "X2")
      (value "SG-210STF 24.0000ML0")
      (footprint "OSC_4-SMD(2.5x2)")
      (description "Oscillator XO 24MHz ±50ppm 15pF CMOS 55% 1.8V/2.5V/3.3V 4-Pin SMD T/R")
      (fields (field (name "MANUFACTURER") "Epson"))
      (libsource (lib "Standard") (part "XTAL-4P"))
    )
  )
  (nets
    (net (code "1") (name "/BT1") (class "Default")
      (node (ref "C26") (pin "2") (pinfunction "2_2") (pintype "passive"))
      (node (ref "D8") (pin "1") (pinfunction "1_1") (pintype "passive"))
      (node (ref "R39") (pin "2") (pinfunction "2_2") (pintype "passive"))
      (node (ref "SW1") (pin "A1") (pinfunction "COM_1_A1") (pintype "passive"))
      (node (ref "U2") (pin "56") (pinfunction "PB4_56") (pintype "passive"))
    )
    (net (code "2") (name "/BT2") (class "Default")
      (node (ref "C27") (pin "2") (pinfunction "2_2") (pintype "passive"))
      (node (ref "D9") (pin "1") (pinfunction "1_1") (pintype "passive"))
      (node (ref "R40") (pin "2") (pinfunction "2_2") (pintype "passive"))
      (node (ref "SW2") (pin "A1") (pinfunction "COM_1_A1") (pintype "passive"))
      (node (ref "U2") (pin "45") (pinfunction "PA12_45") (pintype "passive"))
    )
    (net (code "3") (name "/Blue_Rx") (class "Default")
      (node (ref "R36") (pin "2") (pinfunction "2_2") (pintype "passive"))
      (node (ref "U2") (pin "38") (pinfunction "PC7_38") (pintype "passive"))
    )
    (net (code "4") (name "/Blue_Tx") (class "Default")
      (node (ref "R38") (pin "2") (pinfunction "2_2") (pintype "passive"))
      (node (ref "U2") (pin "44") (pinfunction "PA11_44") (pintype "passive"))
    )
    (net (code "5") (name "/DebugLED_A") (class "Default")
      (node (ref "D5") (pin "2") (pinfunction "Anode_2") (pintype "passive"))
      (node (ref "U2") (pin "11") (pinfunction "PC3_11") (pintype "passive"))
    )
    (net (code "6") (name "/DebugLED_B") (class "Default")
      (node (ref "D6") (pin "2") (pinfunction "Anode_2") (pintype "passive"))
      (node (ref "U2") (pin "24") (pinfunction "PC4_24") (pintype "passive"))
    )
    (net (code "7") (name "/DebugLED_C") (class "Default")
      (node (ref "D7") (pin "2") (pinfunction "Anode_2") (pintype "passive"))
      (node (ref "U2") (pin "25") (pinfunction "PC5_25") (pintype "passive"))
    )
    (net (code "8") (name "/Debug_Rx") (class "Default")
      (node (ref "R34") (pin "2") (pinfunction "2_2") (pintype "passive"))
      (node (ref "U2") (pin "43") (pinfunction "PA10_43") (pintype "passive"))
    )
    (net (code "9") (name "/Debug_Tx") (class "Default")
      (node (ref "R33") (pin "1") (pinfunction "1_1") (pintype "passive"))
      (node (ref "U2") (pin "42") (pinfunction "PA9_42") (pintype "passive"))
    )
    (net (code "10") (name "/ENC_L_A") (class "Default")
      (node (ref "J2") (pin "3") (pinfunction "3_3") (pintype "passive"))
      (node (ref "U2") (pin "59") (pinfunction "PB7_59") (pintype "passive"))
    )
    (net (code "11") (name "/ENC_L_B") (class "Default")
      (node (ref "J2") (pin "2") (pinfunction "2_2") (pintype "passive"))
      (node (ref "U2") (pin "58") (pinfunction "PB6_58") (pintype "passive"))
    )
    (net (code "12") (name "/ENC_R_A") (class "Default")
      (node (ref "J3") (pin "3") (pinfunction "3_3") (pintype "passive"))
      (node (ref "U2") (pin "37") (pinfunction "PC6_37") (pintype "passive"))
    )
    (net (code "13") (name "/ENC_R_B") (class "Default")
      (node (ref "J3") (pin "2") (pinfunction "2_2") (pintype "passive"))
      (node (ref "U2") (pin "57") (pinfunction "PB5_57") (pintype "passive"))
    )
    (net (code "14") (name "/FLASH_CS") (class "Default")
      (node (ref "U2") (pin "51") (pinfunction "PC10_51") (pintype "passive"))
      (node (ref "U5") (pin "1") (pinfunction "CS_1") (pintype "passive"))
    )
    (net (code "15") (name "/FLASH_MISO") (class "Default")
      (node (ref "U2") (pin "52") (pinfunction "PC11_52") (pintype "passive"))
      (node (ref "U5") (pin "2") (pinfunction "DO_2") (pintype "passive"))
    )
    (net (code "16") (name "/FLASH_MOSI") (class "Default")
      (node (ref "U2") (pin "53") (pinfunction "PC12_53") (pintype "passive"))
      (node (ref "U5") (pin "5") (pinfunction "DI_5") (pintype "passive"))
    )
    (net (code "17") (name "/FLASH_SCK") (class "Default")
      (node (ref "U2") (pin "33") (pinfunction "PB12_33") (pintype "passive"))
      (node (ref "U5") (pin "6") (pinfunction "CLK_6") (pintype "passive"))
    )
    (net (code "18") (name "/FLASH_nRST") (class "Default")
      (node (ref "C29") (pin "2") (pinfunction "2_2") (pintype "passive"))
      (node (ref "R42") (pin "2") (pinfunction "2_2") (pintype "passive"))
      (node (ref "U5") (pin "7") (pinfunction "nRST_7") (pintype "passive"))
    )
    (net (code "19") (name "/FLASH_nWP") (class "Default")
      (node (ref "C28") (pin "2") (pinfunction "2_2") (pintype "passive"))
      (node (ref "R41") (pin "2") (pinfunction "2_2") (pintype "passive"))
      (node (ref "U5") (pin "3") (pinfunction "nWP_3") (pintype "passive"))
    )
    (net (code "20") (name "/HSE_IN") (class "Default")
      (node (ref "U2") (pin "5") (pinfunction "PH0-OSC_IN_5") (pintype "passive"))
      (node (ref "X2") (pin "3") (pinfunction "3_3") (pintype "passive"))
    )
    (net (code "21") (name "/IMU_ADDRESS_SEL") (class "Default")
      (node (ref "R4") (pin "1") (pinfunction "1_1") (pintype "passive"))
      (node (ref "U1") (pin "17") (pinfunction "ADDRESS_17") (pintype "passive"))
    )
    (net (code "22") (name "/IMU_nRST") (class "Default")
      (node (ref "R13") (pin "2") (pinfunction "2_2") (pintype "passive"))
      (node (ref "U1") (pin "11") (pinfunction "nRESET_11") (pintype "passive"))
    )
    (net (code "23") (name "/IRLED1") (class "Default")
      (node (ref "R9") (pin "2") (pinfunction "2_2") (pintype "passive"))
      (node (ref "U2") (pin "23") (pinfunction "PA7_23") (pintype "passive"))
    )
    (net (code "24") (name "/IRLED2") (class "Default")
      (node (ref "R10") (pin "2") (pinfunction "2_2") (pintype "passive"))
      (node (ref "U2") (pin "22") (pinfunction "PA6_22") (pintype "passive"))
    )
    (net (code "25") (name "/IRLED3") (class "Default")
      (node (ref "R22") (pin "2") (pinfunction "2_2") (pintype "passive"))
      (node (ref "U2") (pin "20") (pinfunction "PA4_20") (pintype "passive"))
    )
    (net (code "26") (name "/IRLED4") (class "Default")
      (node (ref "R23") (pin "2") (pinfunction "2_2") (pintype "passive"))
      (node (ref "U2") (pin "21") (pinfunction "PA5_21") (pintype "passive"))
    )
    (net (code "27") (name "/MTR_L_CS") (class "Default")
      (node (ref "R32") (pin "1") (pinfunction "1_1") (pintype "passive"))
      (node (ref "U3") (pin "1") (pinfunction "IPROPI_1") (pintype "power_in"))
    )
    (net (code "30") (name "/MTR_L_PWM1") (class "Default")
      (node (ref "U2") (pin "16") (pinfunction "PA2_16") (pintype "passive"))
      (node (ref "U3") (pin "3") (pinfunction "IN1_3") (pintype "input"))
    )
    (net (code "31") (name "/MTR_L_PWM2") (class "Default")
      (node (ref "U2") (pin "17") (pinfunction "PA3_17") (pintype "passive"))
      (node (ref "U3") (pin "2") (pinfunction "IN2_2") (pintype "input"))
    )
    (net (code "32") (name "/MTR_R_CS") (class "Default")
      (node (ref "R37") (pin "1") (pinfunction "1_1") (pintype "passive"))
      (node (ref "U4") (pin "1") (pinfunction "IPROPI_1") (pintype "power_in"))
    )
    (net (code "35") (name "/MTR_R_PWM1") (class "Default")
      (node (ref "U2") (pin "50") (pinfunction "PA15_50") (pintype "passive"))
      (node (ref "U4") (pin "3") (pinfunction "IN1_3") (pintype "input"))
    )
    (net (code "36") (name "/MTR_R_PWM2") (class "Default")
      (node (ref "U2") (pin "55") (pinfunction "PB3_55") (pintype "passive"))
      (node (ref "U4") (pin "2") (pinfunction "IN2_2") (pintype "input"))
    )
    (net (code "37") (name "/PT1") (class "Default")
      (node (ref "Q1") (pin "2") (pinfunction "EMITTER_2") (pintype "passive"))
      (node (ref "R5") (pin "1") (pinfunction "1_1") (pintype "passive"))
      (node (ref "TP1") (pin "1") (pinfunction "1_1") (pintype "passive"))
      (node (ref "U2") (pin "27") (pinfunction "PB1_27") (pintype "passive"))
    )
    (net (code "38") (name "/PT2") (class "Default")
      (node (ref "Q2") (pin "2") (pinfunction "EMITTER_2") (pintype "passive"))
      (node (ref "R6") (pin "1") (pinfunction "1_1") (pintype "passive"))
      (node (ref "TP2") (pin "1") (pinfunction "1_1") (pintype "passive"))
      (node (ref "U2") (pin "26") (pinfunction "PB0_26") (pintype "passive"))
    )
    (net (code "39") (name "/PT3") (class "Default")
      (node (ref "Q5") (pin "2") (pinfunction "EMITTER_2") (pintype "passive"))
      (node (ref "R18") (pin "1") (pinfunction "1_1") (pintype "passive"))
      (node (ref "TP5") (pin "1") (pinfunction "1_1") (pintype "passive"))
      (node (ref "U2") (pin "9") (pinfunction "PC1_9") (pintype "passive"))
    )
    (net (code "40") (name "/PT4") (class "Default")
      (node (ref "Q6") (pin "2") (pinfunction "EMITTER_2") (pintype "passive"))
      (node (ref "R19") (pin "1") (pinfunction "1_1") (pintype "passive"))
      (node (ref "TP6") (pin "1") (pinfunction "1_1") (pintype "passive"))
      (node (ref "U2") (pin "8") (pinfunction "PC0_8") (pintype "passive"))
    )
    (net (code "41") (name "/SWCLK") (class "Default")
      (node (ref "R27") (pin "2") (pinfunction "2_2") (pintype "passive"))
      (node (ref "U2") (pin "49") (pinfunction "PA14_49") (pintype "passive"))
    )
    (net (code "42") (name "/SWDIO") (class "Default")
      (node (ref "R26") (pin "2") (pinfunction "2_2") (pintype "passive"))
      (node (ref "U2") (pin "46") (pinfunction "PA13_46") (pintype "passive"))
    )
    (net (code "43") (name "/Sensor_SCL") (class "Default")
      (node (ref "R17") (pin "2") (pinfunction "2_2") (pintype "passive"))
      (node (ref "U1") (pin "19") (pinfunction "SCL_19") (pintype "passive"))
      (node (ref "U2") (pin "61") (pinfunction "PB8_61") (pintype "passive"))
    )
    (net (code "44") (name "/Sensor_SDA") (class "Default")
      (node (ref "R16") (pin "2") (pinfunction "2_2") (pintype "passive"))
      (node (ref "U1") (pin "20") (pinfunction "SDA_20") (pintype "passive"))
      (node (ref "U2") (pin "62") (pinfunction "PB9_62") (pintype "passive"))
    )
    (net (code "45") (name "/nRST") (class "Default")
      (node (ref "C12") (pin "2") (pinfunction "2_2") (pintype "passive"))
      (node (ref "R30") (pin "1") (pinfunction "1_1") (pintype "passive"))
      (node (ref "U2") (pin "7") (pinfunction "NRST_7") (pintype "passive"))
    )
    (net (code "46") (name "1V8") (class "Default")
      (node (ref "C1") (pin "2") (pinfunction "2_2") (pintype "passive"))
      (node (ref "C2") (pin "2") (pinfunction "2_2") (pintype "passive"))
      (node (ref "C8") (pin "2") (pinfunction "2_2") (pintype "passive"))
      (node (ref "C9") (pin "2") (pinfunction "2_2") (pintype "passive"))
      (node (ref "R1") (pin "2") (pinfunction "2_2") (pintype "passive"))
      (node (ref "R14") (pin "2") (pinfunction "2_2") (pintype "passive"))
      (node (ref "R15") (pin "2") (pinfunction "2_2") (pintype "passive"))
      (node (ref "R2") (pin "2") (pinfunction "2_2") (pintype "passive"))
    )
    (net (code "47") (name "3V3") (class "Default")
      (node (ref "C15") (pin "2") (pinfunction "2_2") (pintype "passive"))
      (node (ref "C16") (pin "2") (pinfunction "2_2") (pintype "passive"))
      (node (ref "C17") (pin "2") (pinfunction "2_2") (pintype "passive"))
      (node (ref "C18") (pin "2") (pinfunction "2_2") (pintype "passive"))
      (node (ref "C19") (pin "2") (pinfunction "2_2") (pintype "passive"))
      (node (ref "C20") (pin "2") (pinfunction "2_2") (pintype "passive"))
      (node (ref "C21") (pin "2") (pinfunction "2_2") (pintype "passive"))
      (node (ref "C22") (pin "2") (pinfunction "2_2") (pintype "passive"))
      (node (ref "C24") (pin "2") (pinfunction "2_2") (pintype "passive"))
      (node (ref "C25") (pin "2") (pinfunction "2_2") (pintype "passive"))
      (node (ref "C4") (pin "1") (pinfunction "1_1") (pintype "passive"))
      (node (ref "C5") (pin "1") (pinfunction "1_1") (pintype "passive"))
      (node (ref "J1") (pin "3") (pinfunction "3_3") (pintype "passive"))
      (node (ref "J2") (pin "4") (pinfunction "4_4") (pintype "passive"))
      (node (ref "J3") (pin "4") (pinfunction "4_4") (pintype "passive"))
      (node (ref "Q1") (pin "1") (pinfunction "COLLECTOR_1") (pintype "passive"))
      (node (ref "Q2") (pin "1") (pinfunction "COLLECTOR_1") (pintype "passive"))
      (node (ref "Q5") (pin "1") (pinfunction "COLLECTOR_1") (pintype "passive"))
      (node (ref "Q6") (pin "1") (pinfunction "COLLECTOR_1") (pintype "passive"))
      (node (ref "R13") (pin "1") (pinfunction "1_1") (pintype "passive"))
      (node (ref "R16") (pin "1") (pinfunction "1_1") (pintype "passive"))
      (node (ref "R17") (pin "1") (pinfunction "1_1") (pintype "passive"))
      (node (ref "R3") (pin "1") (pinfunction "1_1") (pintype "passive"))
      (node (ref "R35") (pin "2") (pinfunction "2_2") (pintype "passive"))
      (node (ref "R39") (pin "1") (pinfunction "1_1") (pintype "passive"))
      (node (ref "R40") (pin "1") (pinfunction "1_1") (pintype "passive"))
      (node (ref "R41") (pin "1") (pinfunction "1_1") (pintype "passive"))
      (node (ref "R42") (pin "1") (pinfunction "1_1") (pintype "passive"))
      (node (ref "U1") (pin "28") (pinfunction "VDDIO_28") (pintype "passive"))
      (node (ref "U1") (pin "3") (pinfunction "VDD_3") (pintype "passive"))
      (node (ref "U2") (pin "1") (pinfunction "VBAT_1") (pintype "passive"))
      (node (ref "U2") (pin "13") (pinfunction "VDDA/VREF+_13") (pintype "passive"))
      (node (ref "U2") (pin "19") (pinfunction "VDD_1_19") (pintype "passive"))
      (node (ref "U2") (pin "32") (pinfunction "VDD_2_32") (pintype "passive"))
      (node (ref "U2") (pin "48") (pinfunction "VDD_3_48") (pintype "passive"))
      (node (ref "U2") (pin "64") (pinfunction "VDD_4_64") (pintype "passive"))
      (node (ref "U3") (pin "4") (pinfunction "VREF_4") (pintype "power_in"))
      (node (ref "U4") (pin "4") (pinfunction "VREF_4") (pintype "power_in"))
      (node (ref "U5") (pin "8") (pinfunction "VCC_8") (pintype "power_in"))
      (node (ref "X2") (pin "1") (pintype "passive"))
      (node (ref "X2") (pin "4") (pinfunction "4_4") (pintype "passive"))
    )
    (net (code "48") (name "6V0") (class "Default")
      (node (ref "C10") (pin "1") (pinfunction "1_1") (pintype "passive"))
      (node (ref "C11") (pin "1") (pinfunction "1_1") (pintype "passive"))
      (node (ref "C13") (pin "1") (pinfunction "1_1") (pintype "passive"))
      (node (ref "C14") (pin "1") (pinfunction "1_1") (pintype "passive"))
      (node (ref "J4") (pin "2") (pinfunction "2_2") (pintype "passive"))
      (node (ref "U3") (pin "5") (pinfunction "VM_5") (pintype "power_in"))
      (node (ref "U4") (pin "5") (pinfunction "VM_5") (pintype "power_in"))
    )
    (net (code "49") (name "GND") (class "Default")
      (node (ref "C1") (pin "1") (pinfunction "1_1") (pintype "passive"))
      (node (ref "C10") (pin "2") (pinfunction "2_2") (pintype "passive"))
      (node (ref "C11") (pin "2") (pinfunction "2_2") (pintype "passive"))
      (node (ref "C12") (pin "1") (pinfunction "1_1") (pintype "passive"))
      (node (ref "C13") (pin "2") (pinfunction "2_2") (pintype "passive"))
      (node (ref "C14") (pin "2") (pinfunction "2_2") (pintype "passive"))
      (node (ref "C15") (pin "1") (pinfunction "1_1") (pintype "passive"))
      (node (ref "C16") (pin "1") (pinfunction "1_1") (pintype "passive"))
      (node (ref "C17") (pin "1") (pinfunction "1_1") (pintype "passive"))
      (node (ref "C18") (pin "1") (pinfunction "1_1") (pintype "passive"))
      (node (ref "C19") (pin "1") (pinfunction "1_1") (pintype "passive"))
      (node (ref "C2") (pin "1") (pinfunction "1_1") (pintype "passive"))
      (node (ref "C20") (pin "1") (pinfunction "1_1") (pintype "passive"))
      (node (ref "C21") (pin "1") (pinfunction "1_1") (pintype "passive"))
      (node (ref "C22") (pin "1") (pinfunction "1_1") (pintype "passive"))
      (node (ref "C23") (pin "1") (pinfunction "1_1") (pintype "passive"))
      (node (ref "C24") (pin "1") (pinfunction "1_1") (pintype "passive"))
      (node (ref "C25") (pin "1") (pinfunction "1_1") (pintype "passive"))
      (node (ref "C26") (pin "1") (pinfunction "1_1") (pintype "passive"))
      (node (ref "C27") (pin "1") (pinfunction "1_1") (pintype "passive"))
      (node (ref "C28") (pin "1") (pinfunction "1_1") (pintype "passive"))
      (node (ref "C29") (pin "1") (pinfunction "1_1") (pintype "passive"))
      (node (ref "C3") (pin "1") (pinfunction "1_1") (pintype "passive"))
      (node (ref "C4") (pin "2") (pinfunction "2_2") (pintype "passive"))
      (node (ref "C5") (pin "2") (pinfunction "2_2") (pintype "passive"))
      (node (ref "C6") (pin "1") (pinfunction "1_1") (pintype "passive"))
      (node (ref "C7") (pin "1") (pinfunction "1_1") (pintype "passive"))
      (node (ref "C8") (pin "1") (pinfunction "1_1") (pintype "passive"))
      (node (ref "C9") (pin "1") (pinfunction "1_1") (pintype "passive"))
      (node (ref "D8") (pin "2") (pinfunction "2_2") (pintype "passive"))
      (node (ref "D9") (pin "2") (pinfunction "2_2") (pintype "passive"))
      (node (ref "J1") (pin "5") (pinfunction "5_5") (pintype "passive"))
      (node (ref "J1") (pin "7") (pinfunction "7_7") (pintype "passive"))
      (node (ref "J2") (pin "1") (pinfunction "1_1") (pintype "passive"))
      (node (ref "J3") (pin "1") (pinfunction "1_1") (pintype "passive"))
      (node (ref "J4") (pin "3") (pinfunction "3_3") (pintype "passive"))
      (node (ref "Q3") (pin "2") (pinfunction "Source_2") (pintype "passive"))
      (node (ref "Q4") (pin "2") (pinfunction "Source_2") (pintype "passive"))
      (node (ref "Q7") (pin "2") (pinfunction "Source_2") (pintype "passive"))
      (node (ref "Q8") (pin "2") (pinfunction "Source_2") (pintype "passive"))
      (node (ref "R11") (pin "2") (pinfunction "2_2") (pintype "passive"))
      (node (ref "R12") (pin "2") (pinfunction "2_2") (pintype "passive"))
      (node (ref "R20") (pin "1") (pinfunction "CCW_1") (pintype "passive"))
      (node (ref "R21") (pin "1") (pinfunction "CCW_1") (pintype "passive"))
      (node (ref "R24") (pin "2") (pinfunction "2_2") (pintype "passive"))
      (node (ref "R25") (pin "2") (pinfunction "2_2") (pintype "passive"))
      (node (ref "R31") (pin "2") (pinfunction "2_2") (pintype "passive"))
      (node (ref "R32") (pin "2") (pinfunction "2_2") (pintype "passive"))
      (node (ref "R37") (pin "2") (pinfunction "2_2") (pintype "passive"))
      (node (ref "R4") (pin "2") (pinfunction "2_2") (pintype "passive"))
      (node (ref "R43") (pin "2") (pinfunction "2_2") (pintype "passive"))
      (node (ref "R44") (pin "2") (pinfunction "2_2") (pintype "passive"))
      (node (ref "R45") (pin "2") (pinfunction "2_2") (pintype "passive"))
      (node (ref "R7") (pin "1") (pinfunction "CCW_1") (pintype "passive"))
      (node (ref "R8") (pin "1") (pinfunction "CCW_1") (pintype "passive"))
      (node (ref "SW1") (pin "B2") (pinfunction "NO_2_B2") (pintype "passive"))
      (node (ref "SW2") (pin "B2") (pinfunction "NO_2_B2") (pintype "passive"))
      (node (ref "U1") (pin "18") (pinfunction "VSS_IO_18") (pintype "passive"))
      (node (ref "U1") (pin "2") (pinfunction "VSS_2") (pintype "passive"))
      (node (ref "U1") (pin "25") (pinfunction "VSS_IO_25") (pintype "passive"))
      (node (ref "U1") (pin "5") (pinfunction "PS1_5") (pintype "passive"))
      (node (ref "U1") (pin "6") (pinfunction "PS0_6") (pintype "passive"))
      (node (ref "U2") (pin "12") (pinfunction "VSSA/VREF-_12") (pintype "passive"))
      (node (ref "U2") (pin "18") (pinfunction "VSS_1_18") (pintype "passive"))
      (node (ref "U2") (pin "31") (pinfunction "VSS_2_31") (pintype "passive"))
      (node (ref "U2") (pin "47") (pinfunction "VSS_3_47") (pintype "passive"))
      (node (ref "U2") (pin "60") (pinfunction "BOOT0_60") (pintype "passive"))
      (node (ref "U2") (pin "63") (pinfunction "VSS_4_63") (pintype "passive"))
      (node (ref "U3") (pin "7") (pinfunction "GND_7") (pintype "power_in"))
      (node (ref "U3") (pin "9") (pinfunction "EPAD_9") (pintype "power_in"))
      (node (ref "U4") (pin "7") (pinfunction "GND_7") (pintype "power_in"))
      (node (ref "U4") (pin "9") (pinfunction "EPAD_9") (pintype "power_in"))
      (node (ref "U5") (pin "4") (pinfunction "VDD_4") (pintype "power_in"))
      (node (ref "X2") (pin "2") (pintype "passive"))
    )
    (net (code "50") (name "Net-(D1-Anode)") (class "Default")
      (node (ref "D1") (pin "2") (pinfunction "Anode_2") (pintype "passive"))
      (node (ref "R1") (pin "1") (pinfunction "1_1") (pintype "passive"))
      (node (ref "TP3") (pin "1") (pinfunction "1_1") (pintype "passive"))
    )
    (net (code "51") (name "Net-(D1-Cathode)") (class "Default")
      (node (ref "D1") (pin "1") (pinfunction "Cathode_1") (pintype "passive"))
      (node (ref "Q3") (pin "3") (pinfunction "Drain_3") (pintype "passive"))
    )
    (net (code "52") (name "Net-(D2-Anode)") (class "Default")
      (node (ref "D2") (pin "2") (pinfunction "Anode_2") (pintype "passive"))
      (node (ref "R2") (pin "1") (pinfunction "1_1") (pintype "passive"))
      (node (ref "TP4") (pin "1") (pinfunction "1_1") (pintype "passive"))
    )
    (net (code "53") (name "Net-(D2-Cathode)") (class "Default")
      (node (ref "D2") (pin "1") (pinfunction "Cathode_1") (pintype "passive"))
      (node (ref "Q4") (pin "3") (pinfunction "Drain_3") (pintype "passive"))
    )
    (net (code "54") (name "Net-(D3-Anode)") (class "Default")
      (node (ref "D3") (pin "2") (pinfunction "Anode_2") (pintype "passive"))
      (node (ref "R14") (pin "1") (pinfunction "1_1") (pintype "passive"))
      (node (ref "TP7") (pin "1") (pinfunction "1_1") (pintype "passive"))
    )
    (net (code "55") (name "Net-(D3-Cathode)") (class "Default")
      (node (ref "D3") (pin "1") (pinfunction "Cathode_1") (pintype "passive"))
      (node (ref "Q7") (pin "3") (pinfunction "Drain_3") (pintype "passive"))
    )
    (net (code "56") (name "Net-(D4-Anode)") (class "Default")
      (node (ref "D4") (pin "2") (pinfunction "Anode_2") (pintype "passive"))
      (node (ref "R15") (pin "1") (pinfunction "1_1") (pintype "passive"))
      (node (ref "TP8") (pin "1") (pinfunction "1_1") (pintype "passive"))
    )
    (net (code "57") (name "Net-(D4-Cathode)") (class "Default")
      (node (ref "D4") (pin "1") (pinfunction "Cathode_1") (pintype "passive"))
      (node (ref "Q8") (pin "3") (pinfunction "Drain_3") (pintype "passive"))
    )
    (net (code "58") (name "Net-(D5-Cathode)") (class "Default")
      (node (ref "D5") (pin "1") (pinfunction "Cathode_1") (pintype "passive"))
      (node (ref "R43") (pin "1") (pinfunction "1_1") (pintype "passive"))
    )
    (net (code "59") (name "Net-(D6-Cathode)") (class "Default")
      (node (ref "D6") (pin "1") (pinfunction "Cathode_1") (pintype "passive"))
      (node (ref "R44") (pin "1") (pinfunction "1_1") (pintype "passive"))
    )
    (net (code "60") (name "Net-(D7-Cathode)") (class "Default")
      (node (ref "D7") (pin "1") (pinfunction "Cathode_1") (pintype "passive"))
      (node (ref "R45") (pin "1") (pinfunction "1_1") (pintype "passive"))
    )
    (net (code "61") (name "Net-(J1-Pad4)") (class "Default")
      (node (ref "J1") (pin "4") (pinfunction "4_4") (pintype "passive"))
      (node (ref "R26") (pin "1") (pinfunction "1_1") (pintype "passive"))
    )
    (net (code "62") (name "Net-(J1-Pad6)") (class "Default")
      (node (ref "J1") (pin "6") (pinfunction "6_6") (pintype "passive"))
      (node (ref "R27") (pin "1") (pinfunction "1_1") (pintype "passive"))
    )
    (net (code "63") (name "Net-(J1-Pad8)") (class "Default")
      (node (ref "J1") (pin "8") (pinfunction "8_8") (pintype "passive"))
      (node (ref "R28") (pin "1") (pinfunction "1_1") (pintype "passive"))
    )
    (net (code "64") (name "Net-(J1-Pad10)") (class "Default")
      (node (ref "J1") (pin "10") (pinfunction "10_10") (pintype "passive"))
      (node (ref "R29") (pin "1") (pinfunction "1_1") (pintype "passive"))
    )
    (net (code "65") (name "Net-(J1-Pad11)") (class "Default")
      (node (ref "J1") (pin "11") (pinfunction "11_11") (pintype "passive"))
      (node (ref "R31") (pin "1") (pinfunction "1_1") (pintype "passive"))
    )
    (net (code "66") (name "Net-(J1-Pad12)") (class "Default")
      (node (ref "J1") (pin "12") (pinfunction "12_12") (pintype "passive"))
      (node (ref "R30") (pin "2") (pinfunction "2_2") (pintype "passive"))
    )
    (net (code "67") (name "Net-(J1-Pad13)") (class "Default")
      (node (ref "J1") (pin "13") (pinfunction "13_13") (pintype "passive"))
      (node (ref "R34") (pin "1") (pinfunction "1_1") (pintype "passive"))
    )
    (net (code "68") (name "Net-(J1-Pad14)") (class "Default")
      (node (ref "J1") (pin "14") (pinfunction "14_14") (pintype "passive"))
      (node (ref "R33") (pin "2") (pinfunction "2_2") (pintype "passive"))
    )
    (net (code "69") (name "Net-(J4-Pad1)") (class "Default")
      (node (ref "J4") (pin "1") (pinfunction "1_1") (pintype "passive"))
      (node (ref "R35") (pin "1") (pinfunction "1_1") (pintype "passive"))
    )
    (net (code "70") (name "Net-(J4-Pad4)") (class "Default")
      (node (ref "J4") (pin "4") (pinfunction "4_4") (pintype "passive"))
      (node (ref "R36") (pin "1") (pinfunction "1_1") (pintype "passive"))
    )
    (net (code "71") (name "Net-(J4-Pad5)") (class "Default")
      (node (ref "J4") (pin "5") (pinfunction "5_5") (pintype "passive"))
      (node (ref "R38") (pin "1") (pinfunction "1_1") (pintype "passive"))
    )
    (net (code "72") (name "Net-(Q3-Gate)") (class "Default")
      (node (ref "Q3") (pin "1") (pinfunction "Gate_1") (pintype "passive"))
      (node (ref "R11") (pin "1") (pinfunction "1_1") (pintype "passive"))
      (node (ref "R9") (pin "1") (pinfunction "1_1") (pintype "passive"))
    )
    (net (code "73") (name "Net-(Q4-Gate)") (class "Default")
      (node (ref "Q4") (pin "1") (pinfunction "Gate_1") (pintype "passive"))
      (node (ref "R10") (pin "1") (pinfunction "1_1") (pintype "passive"))
      (node (ref "R12") (pin "1") (pinfunction "1_1") (pintype "passive"))
    )
    (net (code "74") (name "Net-(Q7-Gate)") (class "Default")
      (node (ref "Q7") (pin "1") (pinfunction "Gate_1") (pintype "passive"))
      (node (ref "R22") (pin "1") (pinfunction "1_1") (pintype "passive"))
      (node (ref "R25") (pin "1") (pinfunction "1_1") (pintype "passive"))
    )
    (net (code "75") (name "Net-(Q8-Gate)") (class "Default")
      (node (ref "Q8") (pin "1") (pinfunction "Gate_1") (pintype "passive"))
      (node (ref "R23") (pin "1") (pinfunction "1_1") (pintype "passive"))
      (node (ref "R24") (pin "1") (pinfunction "1_1") (pintype "passive"))
    )
    (net (code "76") (name "Net-(R7-Wiper)") (class "Default")
      (node (ref "R5") (pin "2") (pinfunction "2_2") (pintype "passive"))
      (node (ref "R7") (pin "2") (pinfunction "Wiper_2") (pintype "passive"))
    )
    (net (code "77") (name "Net-(R8-Wiper)") (class "Default")
      (node (ref "R6") (pin "2") (pinfunction "2_2") (pintype "passive"))
      (node (ref "R8") (pin "2") (pinfunction "Wiper_2") (pintype "passive"))
    )
    (net (code "78") (name "Net-(R20-Wiper)") (class "Default")
      (node (ref "R18") (pin "2") (pinfunction "2_2") (pintype "passive"))
      (node (ref "R20") (pin "2") (pinfunction "Wiper_2") (pintype "passive"))
    )
    (net (code "79") (name "Net-(R21-Wiper)") (class "Default")
      (node (ref "R19") (pin "2") (pinfunction "2_2") (pintype "passive"))
      (node (ref "R21") (pin "2") (pinfunction "Wiper_2") (pintype "passive"))
    )
    (net (code "80") (name "Net-(U1-CAP)") (class "Default")
      (node (ref "C3") (pin "2") (pinfunction "2_2") (pintype "passive"))
      (node (ref "U1") (pin "9") (pinfunction "CAP_9") (pintype "passive"))
    )
    (net (code "81") (name "Net-(U1-XIN32)") (class "Default")
      (node (ref "C6") (pin "2") (pinfunction "2_2") (pintype "passive"))
      (node (ref "U1") (pin "27") (pinfunction "XIN32_27") (pintype "passive"))
      (node (ref "X1") (pin "1") (pintype "passive"))
    )
    (net (code "82") (name "Net-(U1-XOUT32)") (class "Default")
      (node (ref "C7") (pin "2") (pinfunction "2_2") (pintype "passive"))
      (node (ref "U1") (pin "26") (pinfunction "XOUT32_26") (pintype "passive"))
      (node (ref "X1") (pin "2") (pintype "passive"))
    )
    (net (code "83") (name "Net-(U1-nBOOT_LOAD_PIN)") (class "Default")
      (node (ref "R3") (pin "2") (pinfunction "2_2") (pintype "passive"))
      (node (ref "U1") (pin "4") (pinfunction "nBOOT_LOAD_PIN_4") (pintype "passive"))
    )
    (net (code "84") (name "Net-(U2B-VCAP_1)") (class "Default")
      (node (ref "C23") (pin "2") (pinfunction "2_2") (pintype "passive"))
      (node (ref "U2") (pin "30") (pinfunction "VCAP_1_30") (pintype "passive"))
    )
    (net (code "85") (name "Net-(U3-OUT1)") (class "Default")
      (node (ref "J2") (pin "5") (pinfunction "5_5") (pintype "passive"))
      (node (ref "U3") (pin "6") (pinfunction "OUT1_6") (pintype "output"))
    )
    (net (code "86") (name "Net-(U3-OUT2)") (class "Default")
      (node (ref "J2") (pin "6") (pinfunction "6_6") (pintype "passive"))
      (node (ref "U3") (pin "8") (pinfunction "OUT2_8") (pintype "output"))
    )
    (net (code "87") (name "Net-(U4-OUT1)") (class "Default")
      (node (ref "J3") (pin "5") (pinfunction "5_5") (pintype "passive"))
      (node (ref "U4") (pin "6") (pinfunction "OUT1_6") (pintype "output"))
    )
    (net (code "88") (name "Net-(U4-OUT2)") (class "Default")
      (node (ref "J3") (pin "6") (pinfunction "6_6") (pintype "passive"))
      (node (ref "U4") (pin "8") (pinfunction "OUT2_8") (pintype "output"))
    )
    (net (code "89") (name "unconnected-(J1-Pad1)") (class "Default")
      (node (ref "J1") (pin "1") (pinfunction "1_1") (pintype "passive+no_connect"))
    )
    (net (code "90") (name "unconnected-(J1-Pad2)") (class "Default")
      (node (ref "J1") (pin "2") (pinfunction "2_2") (pintype "passive+no_connect"))
    )
    (net (code "91") (name "unconnected-(J1-Pad9)") (class "Default")
      (node (ref "J1") (pin "9") (pinfunction "9_9") (pintype "passive+no_connect"))
    )
    (net (code "92") (name "unconnected-(J4-Pad6)") (class "Default")
      (node (ref "J4") (pin "6") (pinfunction "6_6") (pintype "passive+no_connect"))
    )
    (net (code "93") (name "unconnected-(R7-CW-Pad3)") (class "Default")
      (node (ref "R7") (pin "3") (pinfunction "CW_3") (pintype "passive+no_connect"))
    )
    (net (code "94") (name "unconnected-(R8-CW-Pad3)") (class "Default")
      (node (ref "R8") (pin "3") (pinfunction "CW_3") (pintype "passive+no_connect"))
    )
    (net (code "95") (name "unconnected-(R20-CW-Pad3)") (class "Default")
      (node (ref "R20") (pin "3") (pinfunction "CW_3") (pintype "passive+no_connect"))
    )
    (net (code "96") (name "unconnected-(R21-CW-Pad3)") (class "Default")
      (node (ref "R21") (pin "3") (pinfunction "CW_3") (pintype "passive+no_connect"))
    )
    (net (code "97") (name "unconnected-(R28-Pad2)") (class "Default")
      (node (ref "R28") (pin "2") (pinfunction "2_2") (pintype "passive+no_connect"))
    )
    (net (code "98") (name "unconnected-(R29-Pad2)") (class "Default")
      (node (ref "R29") (pin "2") (pinfunction "2_2") (pintype "passive+no_connect"))
    )
    (net (code "99") (name "unconnected-(SW1-COM_2-PadA2)") (class "Default")
      (node (ref "SW1") (pin "A2") (pinfunction "COM_2_A2") (pintype "passive"))
    )
    (net (code "100") (name "unconnected-(SW1-NO_1-PadB1)") (class "Default")
      (node (ref "SW1") (pin "B1") (pinfunction "NO_1_B1") (pintype "passive"))
    )
    (net (code "101") (name "unconnected-(SW2-COM_2-PadA2)") (class "Default")
      (node (ref "SW2") (pin "A2") (pinfunction "COM_2_A2") (pintype "passive"))
    )
    (net (code "102") (name "unconnected-(SW2-NO_1-PadB1)") (class "Default")
      (node (ref "SW2") (pin "B1") (pinfunction "NO_1_B1") (pintype "passive"))
    )
    (net (code "103") (name "unconnected-(U1-BL_IND-Pad10)") (class "Default")
      (node (ref "U1") (pin "10") (pinfunction "BL_IND_10") (pintype "passive+no_connect"))
    )
    (net (code "104") (name "unconnected-(U1-INT-Pad14)") (class "Default")
      (node (ref "U1") (pin "14") (pinfunction "INT_14") (pintype "passive+no_connect"))
    )
    (net (code "105") (name "unconnected-(U1-PIN1-Pad1)") (class "Default")
      (node (ref "U1") (pin "1") (pinfunction "PIN1_1") (pintype "passive+no_connect"))
    )
    (net (code "106") (name "unconnected-(U1-PIN12-Pad12)") (class "Default")
      (node (ref "U1") (pin "12") (pinfunction "PIN12_12") (pintype "passive+no_connect"))
    )
    (net (code "107") (name "unconnected-(U1-PIN13-Pad13)") (class "Default")
      (node (ref "U1") (pin "13") (pinfunction "PIN13_13") (pintype "passive+no_connect"))
    )
    (net (code "108") (name "unconnected-(U1-PIN15-Pad15)") (class "Default")
      (node (ref "U1") (pin "15") (pinfunction "PIN15_15") (pintype "passive+no_connect"))
    )
    (net (code "109") (name "unconnected-(U1-PIN16-Pad16)") (class "Default")
      (node (ref "U1") (pin "16") (pinfunction "PIN16_16") (pintype "passive+no_connect"))
    )
    (net (code "110") (name "unconnected-(U1-PIN21-Pad21)") (class "Default")
      (node (ref "U1") (pin "21") (pinfunction "PIN21_21") (pintype "passive+no_connect"))
    )
    (net (code "111") (name "unconnected-(U1-PIN22-Pad22)") (class "Default")
      (node (ref "U1") (pin "22") (pinfunction "PIN22_22") (pintype "passive+no_connect"))
    )
    (net (code "112") (name "unconnected-(U1-PIN23-Pad23)") (class "Default")
      (node (ref "U1") (pin "23") (pinfunction "PIN23_23") (pintype "passive+no_connect"))
    )
    (net (code "113") (name "unconnected-(U1-PIN24-Pad24)") (class "Default")
      (node (ref "U1") (pin "24") (pinfunction "PIN24_24") (pintype "passive+no_connect"))
    )
    (net (code "114") (name "unconnected-(U1-SWCLK-Pad8)") (class "Default")
      (node (ref "U1") (pin "8") (pinfunction "SWCLK_8") (pintype "passive+no_connect"))
    )
    (net (code "115") (name "unconnected-(U1-SWDIO-Pad7)") (class "Default")
      (node (ref "U1") (pin "7") (pinfunction "SWDIO_7") (pintype "passive+no_connect"))
    )
    (net (code "116") (name "unconnected-(U2A-PA0-Pad14)") (class "Default")
      (node (ref "U2") (pin "14") (pinfunction "PA0_14") (pintype "passive"))
    )
    (net (code "117") (name "unconnected-(U2A-PA1-Pad15)") (class "Default")
      (node (ref "U2") (pin "15") (pinfunction "PA1_15") (pintype "passive"))
    )
    (net (code "118") (name "unconnected-(U2A-PA8-Pad41)") (class "Default")
      (node (ref "U2") (pin "41") (pinfunction "PA8_41") (pintype "passive"))
    )
    (net (code "119") (name "unconnected-(U2A-PB2-Pad28)") (class "Default")
      (node (ref "U2") (pin "28") (pinfunction "PB2_28") (pintype "passive"))
    )
    (net (code "120") (name "unconnected-(U2A-PB10-Pad29)") (class "Default")
      (node (ref "U2") (pin "29") (pinfunction "PB10_29") (pintype "passive"))
    )
    (net (code "121") (name "unconnected-(U2A-PB13-Pad34)") (class "Default")
      (node (ref "U2") (pin "34") (pinfunction "PB13_34") (pintype "passive"))
    )
    (net (code "122") (name "unconnected-(U2A-PB14-Pad35)") (class "Default")
      (node (ref "U2") (pin "35") (pinfunction "PB14_35") (pintype "passive"))
    )
    (net (code "123") (name "unconnected-(U2A-PB15-Pad36)") (class "Default")
      (node (ref "U2") (pin "36") (pinfunction "PB15_36") (pintype "passive"))
    )
    (net (code "124") (name "unconnected-(U2A-PC2-Pad10)") (class "Default")
      (node (ref "U2") (pin "10") (pinfunction "PC2_10") (pintype "passive"))
    )
    (net (code "125") (name "unconnected-(U2A-PC8-Pad39)") (class "Default")
      (node (ref "U2") (pin "39") (pinfunction "PC8_39") (pintype "passive"))
    )
    (net (code "126") (name "unconnected-(U2A-PC9-Pad40)") (class "Default")
      (node (ref "U2") (pin "40") (pinfunction "PC9_40") (pintype "passive"))
    )
    (net (code "127") (name "unconnected-(U2A-PC13-Pad2)") (class "Default")
      (node (ref "U2") (pin "2") (pinfunction "PC13_2") (pintype "passive"))
    )
    (net (code "128") (name "unconnected-(U2A-PC14-OSC32_IN-Pad3)") (class "Default")
      (node (ref "U2") (pin "3") (pinfunction "PC14-OSC32_IN_3") (pintype "passive"))
    )
    (net (code "129") (name "unconnected-(U2A-PC15-OSC32_OUT-Pad4)") (class "Default")
      (node (ref "U2") (pin "4") (pinfunction "PC15-OSC32_OUT_4") (pintype "passive"))
    )
    (net (code "130") (name "unconnected-(U2A-PD2-Pad54)") (class "Default")
      (node (ref "U2") (pin "54") (pinfunction "PD2_54") (pintype "passive"))
    )
    (net (code "131") (name "unconnected-(U2A-PH1-OSC_OUT-Pad6)") (class "Default")
      (node (ref "U2") (pin "6") (pinfunction "PH1-OSC_OUT_6") (pintype "passive+no_connect"))
    )
  )
)
